# SMT160.net
KiCad netlist of a schematic drawn in Altium Designer
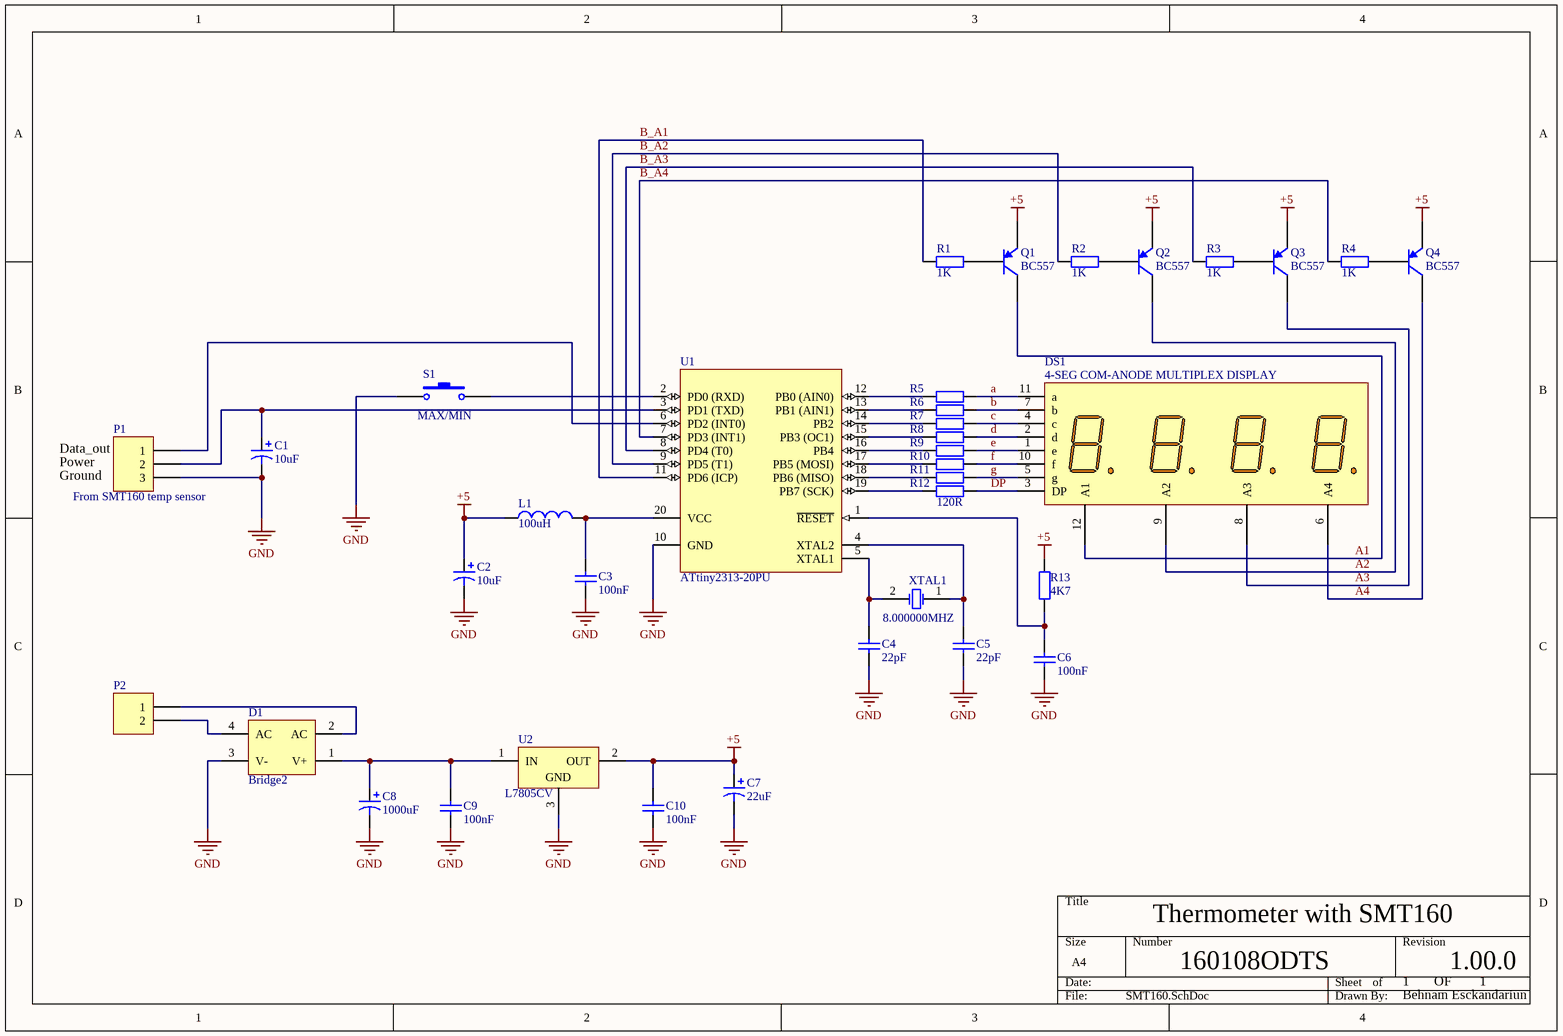
[diagram p0: SMT160.SchDoc]

(export (version "E")
  (design (tool "Eeschema 10.0.6"))
  (components
    (comp (ref "C1")
      (value "10uF")
      (footprint "CAPPR2-5X6.8")
      (description "Polarized Capacitor (Radial)")
      (fields (field (name "Comment") "Cap Pol1") (field (name "PUBLISHER") "Altium Limited"))
      (libsource (lib "Miscellaneous Devices") (part "Cap Pol1"))
    )
    (comp (ref "C2")
      (value "10uF")
      (footprint "CAPPR2-5X6.8")
      (description "Polarized Capacitor (Radial)")
      (fields (field (name "Comment") "Cap Pol1") (field (name "PUBLISHER") "Altium Limited"))
      (libsource (lib "Miscellaneous Devices") (part "Cap Pol1"))
    )
    (comp (ref "C3")
      (value "100nF")
      (footprint "RAD-0.2")
      (description "Capacitor")
      (fields (field (name "Comment") "Cap") (field (name "PUBLISHER") "Altium Limited"))
      (libsource (lib "Miscellaneous Devices") (part "Cap"))
    )
    (comp (ref "C4")
      (value "22pF")
      (footprint "RAD-0.1")
      (description "Capacitor")
      (fields (field (name "Comment") "Cap") (field (name "PUBLISHER") "Altium Limited"))
      (libsource (lib "Miscellaneous Devices") (part "Cap"))
    )
    (comp (ref "C5")
      (value "22pF")
      (footprint "RAD-0.1")
      (description "Capacitor")
      (fields (field (name "Comment") "Cap") (field (name "PUBLISHER") "Altium Limited"))
      (libsource (lib "Miscellaneous Devices") (part "Cap"))
    )
    (comp (ref "C6")
      (value "100nF")
      (footprint "RAD-0.2")
      (description "Capacitor")
      (fields (field (name "Comment") "Cap") (field (name "PUBLISHER") "Altium Limited"))
      (libsource (lib "Miscellaneous Devices") (part "Cap"))
    )
    (comp (ref "C7")
      (value "22uF")
      (footprint "CAPPR2-5X6.8")
      (description "Polarized Capacitor (Radial)")
      (fields (field (name "Comment") "Cap Pol1") (field (name "PUBLISHER") "Altium Limited"))
      (libsource (lib "Miscellaneous Devices") (part "Cap Pol1"))
    )
    (comp (ref "C8")
      (value "1000uF")
      (footprint "CAPPR5-5X5")
      (description "Polarized Capacitor (Radial)")
      (fields (field (name "Comment") "Cap Pol1") (field (name "PUBLISHER") "Altium Limited"))
      (libsource (lib "Miscellaneous Devices") (part "Cap Pol1"))
    )
    (comp (ref "C9")
      (value "100nF")
      (footprint "RAD-0.2")
      (description "Capacitor")
      (fields (field (name "Comment") "Cap") (field (name "PUBLISHER") "Altium Limited"))
      (libsource (lib "Miscellaneous Devices") (part "Cap"))
    )
    (comp (ref "C10")
      (value "100nF")
      (footprint "RAD-0.2")
      (description "Capacitor")
      (fields (field (name "Comment") "Cap") (field (name "PUBLISHER") "Altium Limited"))
      (libsource (lib "Miscellaneous Devices") (part "Cap"))
    )
    (comp (ref "D1")
      (value "Bridge2")
      (footprint "D-46_6A")
      (description "Diode Bridge")
      (fields (field (name "PUBLISHER") "Altium Limited"))
      (libsource (lib "Miscellaneous Devices") (part "Bridge2"))
    )
    (comp (ref "DS1")
      (value "4-SEG COM-ANODE MULTIPLEX DISPLAY")
      (footprint "LED12DIP/4D")
      (libsource (lib "multiplex seven") (part "Component_1"))
    )
    (comp (ref "L1")
      (value "100uH")
      (footprint "axial-0.4")
      (description "Inductor")
      (fields (field (name "PUBLISHER") "Altium Limited"))
      (libsource (lib "Miscellaneous Devices") (part "Inductor"))
    )
    (comp (ref "P1")
      (value "From SMT160 temp sensor")
      (footprint "Cannector-3")
      (description "Header, 3-Pin")
      (fields (field (name "PUBLISHER") "Altium Limited"))
      (libsource (lib "Miscellaneous Connectors") (part "Header 3"))
    )
    (comp (ref "P2")
      (value "Header 2")
      (footprint "Cannector-2")
      (description "Header, 2-Pin")
      (fields (field (name "PUBLISHER") "Altium Limited"))
      (libsource (lib "Miscellaneous Connectors") (part "Header 2"))
    )
    (comp (ref "Q1")
      (value "BC557")
      (footprint "BCY-W3")
      (description "PNP General-purpose Transistor")
      (fields (field (name "PUBLISHER") "Altium Limited"))
      (libsource (lib "Philips Discrete BJT - Low Power") (part "BC557"))
    )
    (comp (ref "Q2")
      (value "BC557")
      (footprint "BCY-W3")
      (description "PNP General-purpose Transistor")
      (fields (field (name "PUBLISHER") "Altium Limited"))
      (libsource (lib "Philips Discrete BJT - Low Power") (part "BC557"))
    )
    (comp (ref "Q3")
      (value "BC557")
      (footprint "BCY-W3")
      (description "PNP General-purpose Transistor")
      (fields (field (name "PUBLISHER") "Altium Limited"))
      (libsource (lib "Philips Discrete BJT - Low Power") (part "BC557"))
    )
    (comp (ref "Q4")
      (value "BC557")
      (footprint "BCY-W3")
      (description "PNP General-purpose Transistor")
      (fields (field (name "PUBLISHER") "Altium Limited"))
      (libsource (lib "Philips Discrete BJT - Low Power") (part "BC557"))
    )
    (comp (ref "R1")
      (value "1K")
      (footprint "AXIAL-0.4")
      (description "Resistor")
      (fields (field (name "Comment") "Res2") (field (name "PUBLISHER") "Altium Limited"))
      (libsource (lib "Miscellaneous Devices") (part "Res2"))
    )
    (comp (ref "R2")
      (value "1K")
      (footprint "AXIAL-0.4")
      (description "Resistor")
      (fields (field (name "Comment") "Res2") (field (name "PUBLISHER") "Altium Limited"))
      (libsource (lib "Miscellaneous Devices") (part "Res2"))
    )
    (comp (ref "R3")
      (value "1K")
      (footprint "AXIAL-0.4")
      (description "Resistor")
      (fields (field (name "Comment") "Res2") (field (name "PUBLISHER") "Altium Limited"))
      (libsource (lib "Miscellaneous Devices") (part "Res2"))
    )
    (comp (ref "R4")
      (value "1K")
      (footprint "AXIAL-0.4")
      (description "Resistor")
      (fields (field (name "Comment") "Res2") (field (name "PUBLISHER") "Altium Limited"))
      (libsource (lib "Miscellaneous Devices") (part "Res2"))
    )
    (comp (ref "R5")
      (value "Res2")
      (footprint "AXIAL-0.4")
      (description "Resistor")
      (fields (field (name "PUBLISHER") "Altium Limited"))
      (libsource (lib "Miscellaneous Devices") (part "Res2"))
    )
    (comp (ref "R6")
      (value "Res2")
      (footprint "AXIAL-0.4")
      (description "Resistor")
      (fields (field (name "PUBLISHER") "Altium Limited"))
      (libsource (lib "Miscellaneous Devices") (part "Res2"))
    )
    (comp (ref "R7")
      (value "Res2")
      (footprint "AXIAL-0.4")
      (description "Resistor")
      (fields (field (name "PUBLISHER") "Altium Limited"))
      (libsource (lib "Miscellaneous Devices") (part "Res2"))
    )
    (comp (ref "R8")
      (value "Res2")
      (footprint "AXIAL-0.4")
      (description "Resistor")
      (fields (field (name "PUBLISHER") "Altium Limited"))
      (libsource (lib "Miscellaneous Devices") (part "Res2"))
    )
    (comp (ref "R9")
      (value "Res2")
      (footprint "AXIAL-0.4")
      (description "Resistor")
      (fields (field (name "PUBLISHER") "Altium Limited"))
      (libsource (lib "Miscellaneous Devices") (part "Res2"))
    )
    (comp (ref "R10")
      (value "Res2")
      (footprint "AXIAL-0.4")
      (description "Resistor")
      (fields (field (name "PUBLISHER") "Altium Limited"))
      (libsource (lib "Miscellaneous Devices") (part "Res2"))
    )
    (comp (ref "R11")
      (value "Res2")
      (footprint "AXIAL-0.4")
      (description "Resistor")
      (fields (field (name "PUBLISHER") "Altium Limited"))
      (libsource (lib "Miscellaneous Devices") (part "Res2"))
    )
    (comp (ref "R12")
      (value "120R")
      (footprint "AXIAL-0.4")
      (description "Resistor")
      (fields (field (name "Comment") "Res2") (field (name "PUBLISHER") "Altium Limited"))
      (libsource (lib "Miscellaneous Devices") (part "Res2"))
    )
    (comp (ref "R13")
      (value "4K7")
      (footprint "AXIAL-0.4")
      (description "Resistor")
      (fields (field (name "Comment") "Res2") (field (name "PUBLISHER") "Altium Limited"))
      (libsource (lib "") (part "Res2_1"))
    )
    (comp (ref "S1")
      (value "MAX/MIN")
      (footprint "SPST-2")
      (description "Switch")
      (fields (field (name "PUBLISHER") "Altium Limited"))
      (libsource (lib "Miscellaneous Devices") (part "SW-PB"))
    )
    (comp (ref "U1")
      (value "ATtiny2313-20PU")
      (footprint "20P3")
      (description "8-Bit AVR Microcontroller with 2K Bytes of In-System Programmable Flash Memory")
      (fields (field (name "PUBLISHER") "Altium Limited"))
      (libsource (lib "Atmel Microcontroller 8-Bit AVR") (part "AT90S2313-10PI"))
    )
    (comp (ref "U2")
      (value "L7805CV")
      (footprint "TO220ABN")
      (description "Positive Voltage Regulator")
      (fields (field (name "PUBLISHER") "Altium Limited"))
      (libsource (lib "ST Power Mgt Voltage Regulator") (part "L7805CV"))
    )
    (comp (ref "XTAL1")
      (value "8.000000MHZ")
      (footprint "XTAL-1")
      (description "Crystal Oscillator")
      (fields (field (name "PUBLISHER") "Altium Limited"))
      (libsource (lib "Miscellaneous Devices") (part "XTAL"))
    )
  )
  (nets
    (net (code "1") (name "+5") (class "Default")
      (node (ref "C10") (pin "2") (pinfunction "2_2") (pintype "passive"))
      (node (ref "C2") (pin "1") (pinfunction "1_1") (pintype "passive"))
      (node (ref "C7") (pin "1") (pinfunction "1_1") (pintype "passive"))
      (node (ref "L1") (pin "1") (pinfunction "1_1") (pintype "passive"))
      (node (ref "Q1") (pin "3") (pinfunction "C_3") (pintype "passive"))
      (node (ref "Q2") (pin "3") (pinfunction "C_3") (pintype "passive"))
      (node (ref "Q3") (pin "3") (pinfunction "C_3") (pintype "passive"))
      (node (ref "Q4") (pin "3") (pinfunction "C_3") (pintype "passive"))
      (node (ref "R13") (pin "2") (pinfunction "2_2") (pintype "passive"))
      (node (ref "U2") (pin "2") (pinfunction "OUT_2") (pintype "power_in"))
    )
    (net (code "2") (name "/A1") (class "Default")
      (node (ref "DS1") (pin "12") (pinfunction "A1_12") (pintype "passive"))
      (node (ref "Q1") (pin "1") (pinfunction "E_1") (pintype "passive"))
    )
    (net (code "3") (name "/A2") (class "Default")
      (node (ref "DS1") (pin "9") (pinfunction "A2_9") (pintype "passive"))
      (node (ref "Q2") (pin "1") (pinfunction "E_1") (pintype "passive"))
    )
    (net (code "4") (name "/A3") (class "Default")
      (node (ref "DS1") (pin "8") (pinfunction "A3_8") (pintype "passive"))
      (node (ref "Q3") (pin "1") (pinfunction "E_1") (pintype "passive"))
    )
    (net (code "5") (name "/A4") (class "Default")
      (node (ref "DS1") (pin "6") (pinfunction "A4_6") (pintype "passive"))
      (node (ref "Q4") (pin "1") (pinfunction "E_1") (pintype "passive"))
    )
    (net (code "6") (name "/B_A1") (class "Default")
      (node (ref "R1") (pin "1") (pinfunction "1_1") (pintype "passive"))
      (node (ref "U1") (pin "11") (pinfunction "PD6_(ICP)_11") (pintype "bidirectional"))
    )
    (net (code "7") (name "/B_A2") (class "Default")
      (node (ref "R2") (pin "1") (pinfunction "1_1") (pintype "passive"))
      (node (ref "U1") (pin "9") (pinfunction "PD5_(T1)_9") (pintype "bidirectional"))
    )
    (net (code "8") (name "/B_A3") (class "Default")
      (node (ref "R3") (pin "1") (pinfunction "1_1") (pintype "passive"))
      (node (ref "U1") (pin "8") (pinfunction "PD4_(T0)_8") (pintype "bidirectional"))
    )
    (net (code "9") (name "/B_A4") (class "Default")
      (node (ref "R4") (pin "1") (pinfunction "1_1") (pintype "passive"))
      (node (ref "U1") (pin "7") (pinfunction "PD3_(INT1)_7") (pintype "bidirectional"))
    )
    (net (code "10") (name "/DP") (class "Default")
      (node (ref "DS1") (pin "3") (pinfunction "DP_3") (pintype "passive"))
      (node (ref "R12") (pin "2") (pinfunction "2_2") (pintype "passive"))
    )
    (net (code "11") (name "/a") (class "Default")
      (node (ref "DS1") (pin "11") (pinfunction "a_11") (pintype "passive"))
      (node (ref "R5") (pin "2") (pinfunction "2_2") (pintype "passive"))
    )
    (net (code "12") (name "/b") (class "Default")
      (node (ref "DS1") (pin "7") (pinfunction "b_7") (pintype "passive"))
      (node (ref "R6") (pin "2") (pinfunction "2_2") (pintype "passive"))
    )
    (net (code "13") (name "/c") (class "Default")
      (node (ref "DS1") (pin "4") (pinfunction "c_4") (pintype "passive"))
      (node (ref "R7") (pin "2") (pinfunction "2_2") (pintype "passive"))
    )
    (net (code "14") (name "/d") (class "Default")
      (node (ref "DS1") (pin "2") (pinfunction "d_2") (pintype "passive"))
      (node (ref "R8") (pin "2") (pinfunction "2_2") (pintype "passive"))
    )
    (net (code "15") (name "/e") (class "Default")
      (node (ref "DS1") (pin "1") (pinfunction "e_1") (pintype "passive"))
      (node (ref "R9") (pin "2") (pinfunction "2_2") (pintype "passive"))
    )
    (net (code "16") (name "/f") (class "Default")
      (node (ref "DS1") (pin "10") (pinfunction "f_10") (pintype "passive"))
      (node (ref "R10") (pin "2") (pinfunction "2_2") (pintype "passive"))
    )
    (net (code "17") (name "/g") (class "Default")
      (node (ref "DS1") (pin "5") (pinfunction "g_5") (pintype "passive"))
      (node (ref "R11") (pin "2") (pinfunction "2_2") (pintype "passive"))
    )
    (net (code "18") (name "GND") (class "Default")
      (node (ref "C1") (pin "2") (pinfunction "2_2") (pintype "passive"))
      (node (ref "C10") (pin "1") (pinfunction "1_1") (pintype "passive"))
      (node (ref "C2") (pin "2") (pinfunction "2_2") (pintype "passive"))
      (node (ref "C3") (pin "1") (pinfunction "1_1") (pintype "passive"))
      (node (ref "C4") (pin "1") (pinfunction "1_1") (pintype "passive"))
      (node (ref "C5") (pin "1") (pinfunction "1_1") (pintype "passive"))
      (node (ref "C6") (pin "1") (pinfunction "1_1") (pintype "passive"))
      (node (ref "C7") (pin "2") (pinfunction "2_2") (pintype "passive"))
      (node (ref "C8") (pin "2") (pinfunction "2_2") (pintype "passive"))
      (node (ref "C9") (pin "1") (pinfunction "1_1") (pintype "passive"))
      (node (ref "D1") (pin "3") (pinfunction "V-_3") (pintype "passive"))
      (node (ref "P1") (pin "3") (pinfunction "3_3") (pintype "passive"))
      (node (ref "S1") (pin "1") (pinfunction "1_1") (pintype "passive"))
      (node (ref "U1") (pin "10") (pinfunction "GND_10") (pintype "power_in"))
      (node (ref "U2") (pin "3") (pinfunction "GND_3") (pintype "power_in"))
    )
    (net (code "19") (name "Net-(D1-AC-Pad2)") (class "Default")
      (node (ref "D1") (pin "2") (pinfunction "AC_2") (pintype "passive"))
      (node (ref "P2") (pin "1") (pinfunction "1_1") (pintype "passive"))
    )
    (net (code "20") (name "Net-(D1-AC-Pad4)") (class "Default")
      (node (ref "D1") (pin "4") (pinfunction "AC_4") (pintype "passive"))
      (node (ref "P2") (pin "2") (pinfunction "2_2") (pintype "passive"))
    )
    (net (code "21") (name "Net-(D1-V+)") (class "Default")
      (node (ref "C8") (pin "1") (pinfunction "1_1") (pintype "passive"))
      (node (ref "C9") (pin "2") (pinfunction "2_2") (pintype "passive"))
      (node (ref "D1") (pin "1") (pinfunction "V+_1") (pintype "passive"))
      (node (ref "U2") (pin "1") (pinfunction "IN_1") (pintype "power_in"))
    )
    (net (code "22") (name "Net-(Q1-B)") (class "Default")
      (node (ref "Q1") (pin "2") (pinfunction "B_2") (pintype "passive"))
      (node (ref "R1") (pin "2") (pinfunction "2_2") (pintype "passive"))
    )
    (net (code "23") (name "Net-(Q2-B)") (class "Default")
      (node (ref "Q2") (pin "2") (pinfunction "B_2") (pintype "passive"))
      (node (ref "R2") (pin "2") (pinfunction "2_2") (pintype "passive"))
    )
    (net (code "24") (name "Net-(Q3-B)") (class "Default")
      (node (ref "Q3") (pin "2") (pinfunction "B_2") (pintype "passive"))
      (node (ref "R3") (pin "2") (pinfunction "2_2") (pintype "passive"))
    )
    (net (code "25") (name "Net-(Q4-B)") (class "Default")
      (node (ref "Q4") (pin "2") (pinfunction "B_2") (pintype "passive"))
      (node (ref "R4") (pin "2") (pinfunction "2_2") (pintype "passive"))
    )
    (net (code "26") (name "Net-(U1-PB0_(AIN0))") (class "Default")
      (node (ref "R5") (pin "1") (pinfunction "1_1") (pintype "passive"))
      (node (ref "U1") (pin "12") (pinfunction "PB0_(AIN0)_12") (pintype "bidirectional"))
    )
    (net (code "27") (name "Net-(U1-PB1_(AIN1))") (class "Default")
      (node (ref "R6") (pin "1") (pinfunction "1_1") (pintype "passive"))
      (node (ref "U1") (pin "13") (pinfunction "PB1_(AIN1)_13") (pintype "bidirectional"))
    )
    (net (code "28") (name "Net-(U1-PB2)") (class "Default")
      (node (ref "R7") (pin "1") (pinfunction "1_1") (pintype "passive"))
      (node (ref "U1") (pin "14") (pinfunction "PB2_14") (pintype "bidirectional"))
    )
    (net (code "29") (name "Net-(U1-PB3_(OC1))") (class "Default")
      (node (ref "R8") (pin "1") (pinfunction "1_1") (pintype "passive"))
      (node (ref "U1") (pin "15") (pinfunction "PB3_(OC1)_15") (pintype "bidirectional"))
    )
    (net (code "30") (name "Net-(U1-PB4)") (class "Default")
      (node (ref "R9") (pin "1") (pinfunction "1_1") (pintype "passive"))
      (node (ref "U1") (pin "16") (pinfunction "PB4_16") (pintype "bidirectional"))
    )
    (net (code "31") (name "Net-(U1-PB5_(MOSI))") (class "Default")
      (node (ref "R10") (pin "1") (pinfunction "1_1") (pintype "passive"))
      (node (ref "U1") (pin "17") (pinfunction "PB5_(MOSI)_17") (pintype "bidirectional"))
    )
    (net (code "32") (name "Net-(U1-PB6_(MISO))") (class "Default")
      (node (ref "R11") (pin "1") (pinfunction "1_1") (pintype "passive"))
      (node (ref "U1") (pin "18") (pinfunction "PB6_(MISO)_18") (pintype "bidirectional"))
    )
    (net (code "33") (name "Net-(U1-PB7_(SCK))") (class "Default")
      (node (ref "R12") (pin "1") (pinfunction "1_1") (pintype "passive"))
      (node (ref "U1") (pin "19") (pinfunction "PB7_(SCK)_19") (pintype "bidirectional"))
    )
    (net (code "34") (name "Net-(U1-PD0_(RXD))") (class "Default")
      (node (ref "S1") (pin "2") (pinfunction "2_2") (pintype "passive"))
      (node (ref "U1") (pin "2") (pinfunction "PD0_(RXD)_2") (pintype "bidirectional"))
    )
    (net (code "35") (name "Net-(U1-PD1_(TXD))") (class "Default")
      (node (ref "C1") (pin "1") (pinfunction "1_1") (pintype "passive"))
      (node (ref "P1") (pin "2") (pinfunction "2_2") (pintype "passive"))
      (node (ref "U1") (pin "3") (pinfunction "PD1_(TXD)_3") (pintype "bidirectional"))
    )
    (net (code "36") (name "Net-(U1-PD2_(INT0))") (class "Default")
      (node (ref "P1") (pin "1") (pinfunction "1_1") (pintype "passive"))
      (node (ref "U1") (pin "6") (pinfunction "PD2_(INT0)_6") (pintype "bidirectional"))
    )
    (net (code "37") (name "Net-(U1-VCC)") (class "Default")
      (node (ref "C3") (pin "2") (pinfunction "2_2") (pintype "passive"))
      (node (ref "L1") (pin "2") (pinfunction "2_2") (pintype "passive"))
      (node (ref "U1") (pin "20") (pinfunction "VCC_20") (pintype "power_in"))
    )
    (net (code "38") (name "Net-(U1-XTAL1)") (class "Default")
      (node (ref "C4") (pin "2") (pinfunction "2_2") (pintype "passive"))
      (node (ref "U1") (pin "5") (pinfunction "XTAL1_5") (pintype "passive"))
      (node (ref "XTAL1") (pin "2") (pinfunction "OSC2_2") (pintype "passive"))
    )
    (net (code "39") (name "Net-(U1-XTAL2)") (class "Default")
      (node (ref "C5") (pin "2") (pinfunction "2_2") (pintype "passive"))
      (node (ref "U1") (pin "4") (pinfunction "XTAL2_4") (pintype "passive"))
      (node (ref "XTAL1") (pin "1") (pinfunction "OSC1_1") (pintype "passive"))
    )
    (net (code "40") (name "Net-(U1-~{RESET})") (class "Default")
      (node (ref "C6") (pin "2") (pinfunction "2_2") (pintype "passive"))
      (node (ref "R13") (pin "1") (pinfunction "1_1") (pintype "passive"))
      (node (ref "U1") (pin "1") (pinfunction "~{RESET}_1") (pintype "input"))
    )
  )
)
